# 4x4-keyboard.net
KiCad netlist of a schematic drawn in EAGLE
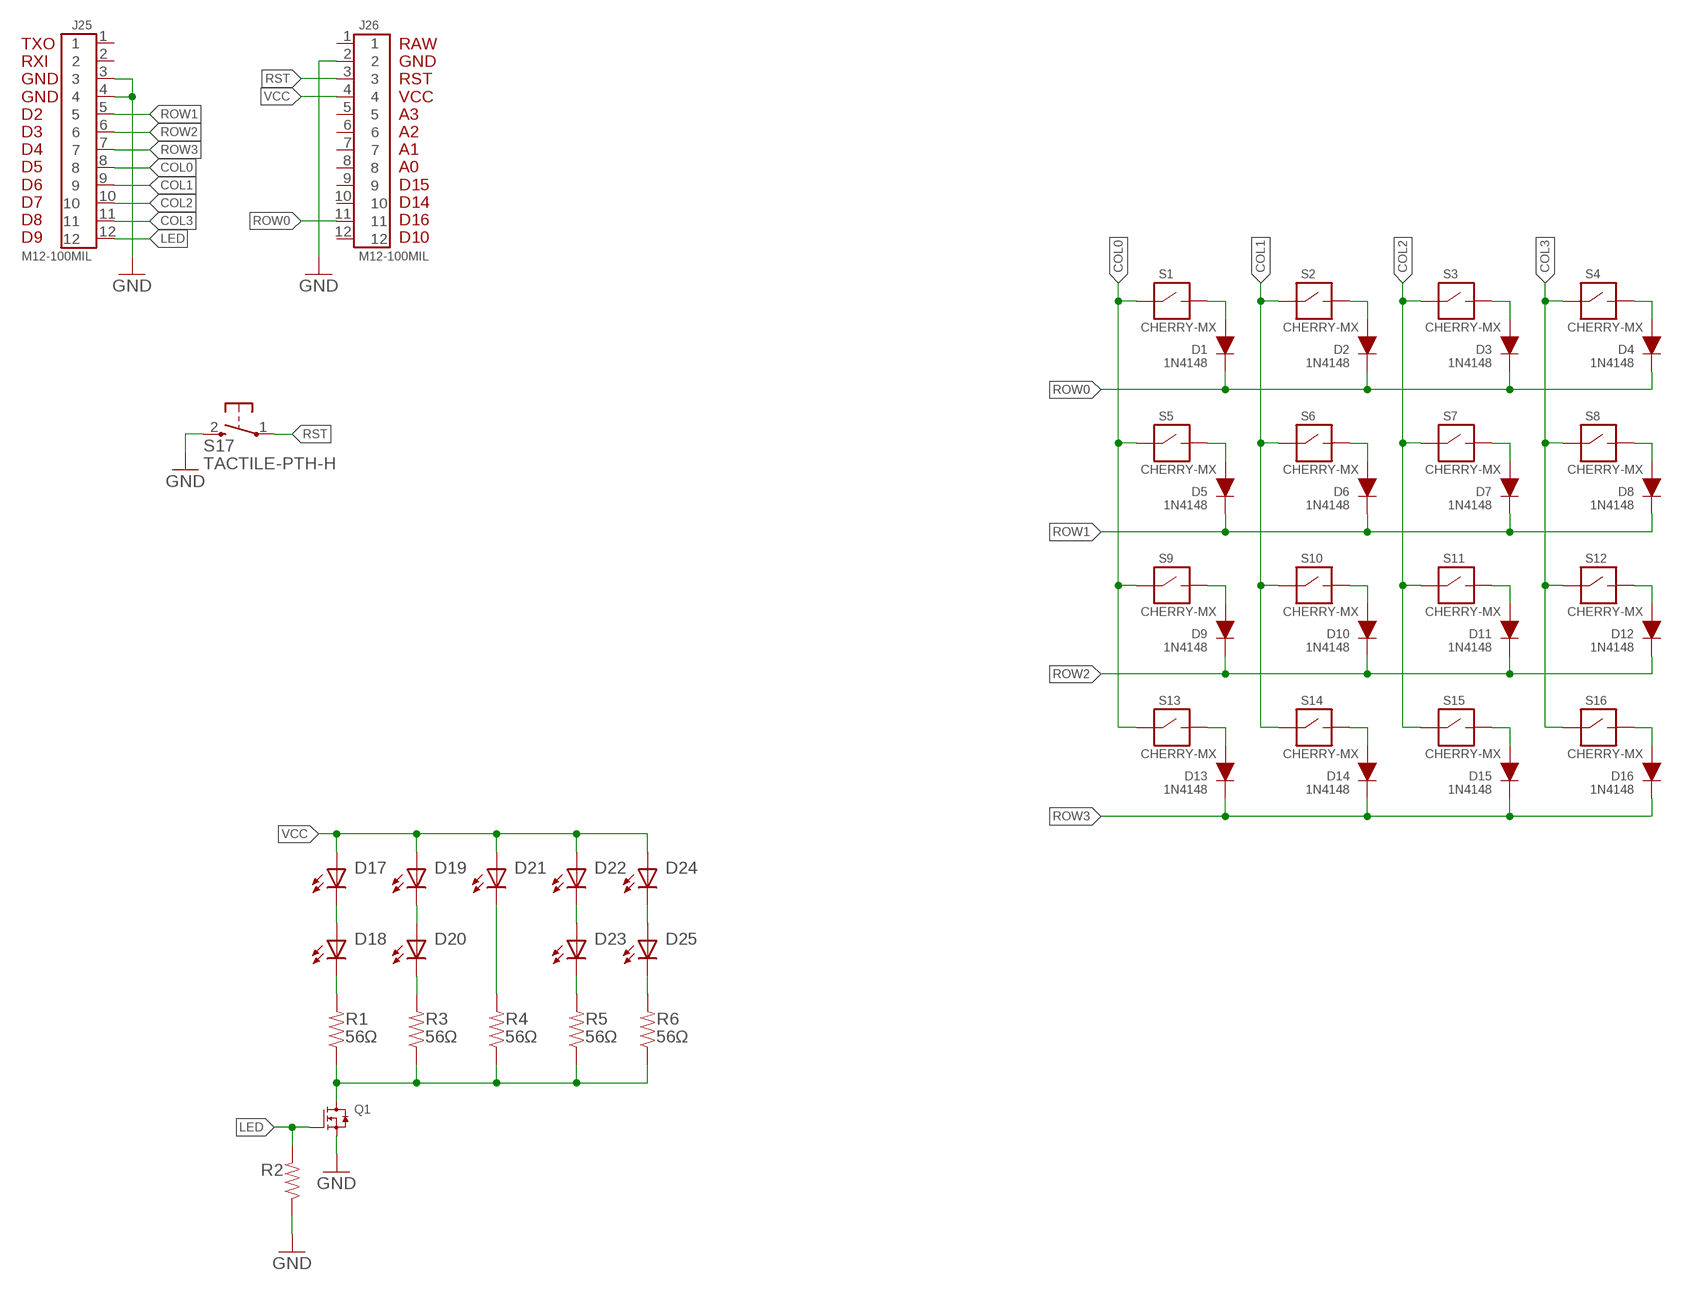
[diagram p0: schematic, sheet 1]

(export (version "E")
  (design (tool "Eeschema 10.0.6"))
  (components
    (comp (ref "D1")
      (value "1N4148")
      (footprint "eagle-import:DIODE-PTH")
      (libsource (lib "eagle-import") (part "DIODE-PTH"))
    )
    (comp (ref "D2")
      (value "1N4148")
      (footprint "eagle-import:DIODE-PTH")
      (libsource (lib "eagle-import") (part "DIODE-PTH"))
    )
    (comp (ref "D3")
      (value "1N4148")
      (footprint "eagle-import:DIODE-PTH")
      (libsource (lib "eagle-import") (part "DIODE-PTH"))
    )
    (comp (ref "D4")
      (value "1N4148")
      (footprint "eagle-import:DIODE-PTH")
      (libsource (lib "eagle-import") (part "DIODE-PTH"))
    )
    (comp (ref "D5")
      (value "1N4148")
      (footprint "eagle-import:DIODE-PTH")
      (libsource (lib "eagle-import") (part "DIODE-PTH"))
    )
    (comp (ref "D6")
      (value "1N4148")
      (footprint "eagle-import:DIODE-PTH")
      (libsource (lib "eagle-import") (part "DIODE-PTH"))
    )
    (comp (ref "D7")
      (value "1N4148")
      (footprint "eagle-import:DIODE-PTH")
      (libsource (lib "eagle-import") (part "DIODE-PTH"))
    )
    (comp (ref "D8")
      (value "1N4148")
      (footprint "eagle-import:DIODE-PTH")
      (libsource (lib "eagle-import") (part "DIODE-PTH"))
    )
    (comp (ref "D9")
      (value "1N4148")
      (footprint "eagle-import:DIODE-PTH")
      (libsource (lib "eagle-import") (part "DIODE-PTH"))
    )
    (comp (ref "D10")
      (value "1N4148")
      (footprint "eagle-import:DIODE-PTH")
      (libsource (lib "eagle-import") (part "DIODE-PTH"))
    )
    (comp (ref "D11")
      (value "1N4148")
      (footprint "eagle-import:DIODE-PTH")
      (libsource (lib "eagle-import") (part "DIODE-PTH"))
    )
    (comp (ref "D12")
      (value "1N4148")
      (footprint "eagle-import:DIODE-PTH")
      (libsource (lib "eagle-import") (part "DIODE-PTH"))
    )
    (comp (ref "D13")
      (value "1N4148")
      (footprint "eagle-import:DIODE-PTH")
      (libsource (lib "eagle-import") (part "DIODE-PTH"))
    )
    (comp (ref "D14")
      (value "1N4148")
      (footprint "eagle-import:DIODE-PTH")
      (libsource (lib "eagle-import") (part "DIODE-PTH"))
    )
    (comp (ref "D15")
      (value "1N4148")
      (footprint "eagle-import:DIODE-PTH")
      (libsource (lib "eagle-import") (part "DIODE-PTH"))
    )
    (comp (ref "D16")
      (value "1N4148")
      (footprint "eagle-import:DIODE-PTH")
      (libsource (lib "eagle-import") (part "DIODE-PTH"))
    )
    (comp (ref "D17")
      (value "LED-3MM")
      (footprint "eagle-import:3MM-LED")
      (libsource (lib "eagle-import") (part "LED-3MM"))
    )
    (comp (ref "D18")
      (value "LED-3MM")
      (footprint "eagle-import:3MM-LED")
      (libsource (lib "eagle-import") (part "LED-3MM"))
    )
    (comp (ref "D19")
      (value "LED-3MM")
      (footprint "eagle-import:3MM-LED")
      (libsource (lib "eagle-import") (part "LED-3MM"))
    )
    (comp (ref "D20")
      (value "LED-3MM")
      (footprint "eagle-import:3MM-LED")
      (libsource (lib "eagle-import") (part "LED-3MM"))
    )
    (comp (ref "D21")
      (value "LED-3MM")
      (footprint "eagle-import:3MM-LED")
      (libsource (lib "eagle-import") (part "LED-3MM"))
    )
    (comp (ref "D22")
      (value "LED-3MM")
      (footprint "eagle-import:3MM-LED")
      (libsource (lib "eagle-import") (part "LED-3MM"))
    )
    (comp (ref "D23")
      (value "LED-3MM")
      (footprint "eagle-import:3MM-LED")
      (libsource (lib "eagle-import") (part "LED-3MM"))
    )
    (comp (ref "D24")
      (value "LED-3MM")
      (footprint "eagle-import:3MM-LED")
      (libsource (lib "eagle-import") (part "LED-3MM"))
    )
    (comp (ref "D25")
      (value "LED-3MM")
      (footprint "eagle-import:3MM-LED")
      (libsource (lib "eagle-import") (part "LED-3MM"))
    )
    (comp (ref "J25")
      (value "M12-100MIL")
      (footprint "eagle-import:M12X1")
      (libsource (lib "eagle-import") (part "M12-100MIL"))
    )
    (comp (ref "J26")
      (value "M12-100MIL")
      (footprint "eagle-import:M12X1")
      (libsource (lib "eagle-import") (part "M12-100MIL"))
    )
    (comp (ref "Q1")
      (value "N-MOSFET-TO-92")
      (footprint "eagle-import:TO-92-3")
      (libsource (lib "eagle-import") (part "N-MOSFET-TO-92"))
    )
    (comp (ref "R1")
      (value "56Ω")
      (footprint "eagle-import:RESISTOR-PTH")
      (libsource (lib "eagle-import") (part "RESISTOR-PTH"))
    )
    (comp (ref "R2")
      (value "RESISTOR-PTH")
      (footprint "eagle-import:RESISTOR-PTH")
      (libsource (lib "eagle-import") (part "RESISTOR-PTH"))
    )
    (comp (ref "R3")
      (value "56Ω")
      (footprint "eagle-import:RESISTOR-PTH")
      (libsource (lib "eagle-import") (part "RESISTOR-PTH"))
    )
    (comp (ref "R4")
      (value "56Ω")
      (footprint "eagle-import:RESISTOR-PTH")
      (libsource (lib "eagle-import") (part "RESISTOR-PTH"))
    )
    (comp (ref "R5")
      (value "56Ω")
      (footprint "eagle-import:RESISTOR-PTH")
      (libsource (lib "eagle-import") (part "RESISTOR-PTH"))
    )
    (comp (ref "R6")
      (value "56Ω")
      (footprint "eagle-import:RESISTOR-PTH")
      (libsource (lib "eagle-import") (part "RESISTOR-PTH"))
    )
    (comp (ref "S1")
      (value "CHERRY-MX")
      (footprint "eagle-import:CHERRY-MX")
      (libsource (lib "eagle-import") (part "CHERRY-MX"))
    )
    (comp (ref "S2")
      (value "CHERRY-MX")
      (footprint "eagle-import:CHERRY-MX")
      (libsource (lib "eagle-import") (part "CHERRY-MX"))
    )
    (comp (ref "S3")
      (value "CHERRY-MX")
      (footprint "eagle-import:CHERRY-MX")
      (libsource (lib "eagle-import") (part "CHERRY-MX"))
    )
    (comp (ref "S4")
      (value "CHERRY-MX")
      (footprint "eagle-import:CHERRY-MX")
      (libsource (lib "eagle-import") (part "CHERRY-MX"))
    )
    (comp (ref "S5")
      (value "CHERRY-MX")
      (footprint "eagle-import:CHERRY-MX")
      (libsource (lib "eagle-import") (part "CHERRY-MX"))
    )
    (comp (ref "S6")
      (value "CHERRY-MX")
      (footprint "eagle-import:CHERRY-MX")
      (libsource (lib "eagle-import") (part "CHERRY-MX"))
    )
    (comp (ref "S7")
      (value "CHERRY-MX")
      (footprint "eagle-import:CHERRY-MX")
      (libsource (lib "eagle-import") (part "CHERRY-MX"))
    )
    (comp (ref "S8")
      (value "CHERRY-MX")
      (footprint "eagle-import:CHERRY-MX")
      (libsource (lib "eagle-import") (part "CHERRY-MX"))
    )
    (comp (ref "S9")
      (value "CHERRY-MX")
      (footprint "eagle-import:CHERRY-MX")
      (libsource (lib "eagle-import") (part "CHERRY-MX"))
    )
    (comp (ref "S10")
      (value "CHERRY-MX")
      (footprint "eagle-import:CHERRY-MX")
      (libsource (lib "eagle-import") (part "CHERRY-MX"))
    )
    (comp (ref "S11")
      (value "CHERRY-MX")
      (footprint "eagle-import:CHERRY-MX")
      (libsource (lib "eagle-import") (part "CHERRY-MX"))
    )
    (comp (ref "S12")
      (value "CHERRY-MX")
      (footprint "eagle-import:CHERRY-MX")
      (libsource (lib "eagle-import") (part "CHERRY-MX"))
    )
    (comp (ref "S13")
      (value "CHERRY-MX")
      (footprint "eagle-import:CHERRY-MX")
      (libsource (lib "eagle-import") (part "CHERRY-MX"))
    )
    (comp (ref "S14")
      (value "CHERRY-MX")
      (footprint "eagle-import:CHERRY-MX")
      (libsource (lib "eagle-import") (part "CHERRY-MX"))
    )
    (comp (ref "S15")
      (value "CHERRY-MX")
      (footprint "eagle-import:CHERRY-MX")
      (libsource (lib "eagle-import") (part "CHERRY-MX"))
    )
    (comp (ref "S16")
      (value "CHERRY-MX")
      (footprint "eagle-import:CHERRY-MX")
      (libsource (lib "eagle-import") (part "CHERRY-MX"))
    )
    (comp (ref "S17")
      (value "TACTILE-PTH-H")
      (footprint "eagle-import:TACTILE-HORIZONTAL")
      (libsource (lib "eagle-import") (part "TACTILE-PTH-H"))
    )
  )
  (nets
    (net (code "1") (name "COL0") (class "Default")
      (node (ref "J25") (pin "8") (pinfunction "8_8") (pintype "bidirectional"))
      (node (ref "S1") (pin "S1") (pinfunction "S1_S1") (pintype "passive"))
      (node (ref "S1") (pin "S4") (pinfunction "S1_S4") (pintype "passive"))
      (node (ref "S13") (pin "S1") (pinfunction "S1_S1") (pintype "passive"))
      (node (ref "S13") (pin "S4") (pinfunction "S1_S4") (pintype "passive"))
      (node (ref "S5") (pin "S1") (pinfunction "S1_S1") (pintype "passive"))
      (node (ref "S5") (pin "S4") (pinfunction "S1_S4") (pintype "passive"))
      (node (ref "S9") (pin "S1") (pinfunction "S1_S1") (pintype "passive"))
      (node (ref "S9") (pin "S4") (pinfunction "S1_S4") (pintype "passive"))
    )
    (net (code "2") (name "COL1") (class "Default")
      (node (ref "J25") (pin "9") (pinfunction "9_9") (pintype "bidirectional"))
      (node (ref "S10") (pin "S1") (pinfunction "S1_S1") (pintype "passive"))
      (node (ref "S10") (pin "S4") (pinfunction "S1_S4") (pintype "passive"))
      (node (ref "S14") (pin "S1") (pinfunction "S1_S1") (pintype "passive"))
      (node (ref "S14") (pin "S4") (pinfunction "S1_S4") (pintype "passive"))
      (node (ref "S2") (pin "S1") (pinfunction "S1_S1") (pintype "passive"))
      (node (ref "S2") (pin "S4") (pinfunction "S1_S4") (pintype "passive"))
      (node (ref "S6") (pin "S1") (pinfunction "S1_S1") (pintype "passive"))
      (node (ref "S6") (pin "S4") (pinfunction "S1_S4") (pintype "passive"))
    )
    (net (code "3") (name "COL2") (class "Default")
      (node (ref "J25") (pin "10") (pinfunction "10_10") (pintype "bidirectional"))
      (node (ref "S11") (pin "S1") (pinfunction "S1_S1") (pintype "passive"))
      (node (ref "S11") (pin "S4") (pinfunction "S1_S4") (pintype "passive"))
      (node (ref "S15") (pin "S1") (pinfunction "S1_S1") (pintype "passive"))
      (node (ref "S15") (pin "S4") (pinfunction "S1_S4") (pintype "passive"))
      (node (ref "S3") (pin "S1") (pinfunction "S1_S1") (pintype "passive"))
      (node (ref "S3") (pin "S4") (pinfunction "S1_S4") (pintype "passive"))
      (node (ref "S7") (pin "S1") (pinfunction "S1_S1") (pintype "passive"))
      (node (ref "S7") (pin "S4") (pinfunction "S1_S4") (pintype "passive"))
    )
    (net (code "4") (name "COL3") (class "Default")
      (node (ref "J25") (pin "11") (pinfunction "11_11") (pintype "bidirectional"))
      (node (ref "S12") (pin "S1") (pinfunction "S1_S1") (pintype "passive"))
      (node (ref "S12") (pin "S4") (pinfunction "S1_S4") (pintype "passive"))
      (node (ref "S16") (pin "S1") (pinfunction "S1_S1") (pintype "passive"))
      (node (ref "S16") (pin "S4") (pinfunction "S1_S4") (pintype "passive"))
      (node (ref "S4") (pin "S1") (pinfunction "S1_S1") (pintype "passive"))
      (node (ref "S4") (pin "S4") (pinfunction "S1_S4") (pintype "passive"))
      (node (ref "S8") (pin "S1") (pinfunction "S1_S1") (pintype "passive"))
      (node (ref "S8") (pin "S4") (pinfunction "S1_S4") (pintype "passive"))
    )
    (net (code "5") (name "GND") (class "Default")
      (node (ref "J25") (pin "3") (pinfunction "3_3") (pintype "bidirectional"))
      (node (ref "J25") (pin "4") (pinfunction "4_4") (pintype "bidirectional"))
      (node (ref "J26") (pin "2") (pinfunction "2_2") (pintype "bidirectional"))
      (node (ref "Q1") (pin "1") (pinfunction "SOURCE_1") (pintype "bidirectional"))
      (node (ref "R2") (pin "P$1") (pinfunction "1_P$1") (pintype "passive"))
      (node (ref "S17") (pin "2") (pinfunction "3_2") (pintype "passive"))
    )
    (net (code "6") (name "LED") (class "Default")
      (node (ref "J25") (pin "12") (pinfunction "12_12") (pintype "bidirectional"))
      (node (ref "Q1") (pin "2") (pinfunction "GATE_2") (pintype "bidirectional"))
      (node (ref "R2") (pin "P$2") (pinfunction "2_P$2") (pintype "passive"))
    )
    (net (code "7") (name "Net-(D1-PadA)") (class "Default")
      (node (ref "D1") (pin "A") (pinfunction "A_A") (pintype "bidirectional"))
      (node (ref "S1") (pin "S2") (pinfunction "S2_S2") (pintype "passive"))
      (node (ref "S1") (pin "S3") (pinfunction "S2_S3") (pintype "passive"))
    )
    (net (code "8") (name "Net-(D2-PadA)") (class "Default")
      (node (ref "D2") (pin "A") (pinfunction "A_A") (pintype "bidirectional"))
      (node (ref "S2") (pin "S2") (pinfunction "S2_S2") (pintype "passive"))
      (node (ref "S2") (pin "S3") (pinfunction "S2_S3") (pintype "passive"))
    )
    (net (code "9") (name "Net-(D3-PadA)") (class "Default")
      (node (ref "D3") (pin "A") (pinfunction "A_A") (pintype "bidirectional"))
      (node (ref "S3") (pin "S2") (pinfunction "S2_S2") (pintype "passive"))
      (node (ref "S3") (pin "S3") (pinfunction "S2_S3") (pintype "passive"))
    )
    (net (code "10") (name "Net-(D4-PadA)") (class "Default")
      (node (ref "D4") (pin "A") (pinfunction "A_A") (pintype "bidirectional"))
      (node (ref "S4") (pin "S2") (pinfunction "S2_S2") (pintype "passive"))
      (node (ref "S4") (pin "S3") (pinfunction "S2_S3") (pintype "passive"))
    )
    (net (code "11") (name "Net-(D5-PadA)") (class "Default")
      (node (ref "D5") (pin "A") (pinfunction "A_A") (pintype "bidirectional"))
      (node (ref "S5") (pin "S2") (pinfunction "S2_S2") (pintype "passive"))
      (node (ref "S5") (pin "S3") (pinfunction "S2_S3") (pintype "passive"))
    )
    (net (code "12") (name "Net-(D6-PadA)") (class "Default")
      (node (ref "D6") (pin "A") (pinfunction "A_A") (pintype "bidirectional"))
      (node (ref "S6") (pin "S2") (pinfunction "S2_S2") (pintype "passive"))
      (node (ref "S6") (pin "S3") (pinfunction "S2_S3") (pintype "passive"))
    )
    (net (code "13") (name "Net-(D7-PadA)") (class "Default")
      (node (ref "D7") (pin "A") (pinfunction "A_A") (pintype "bidirectional"))
      (node (ref "S7") (pin "S2") (pinfunction "S2_S2") (pintype "passive"))
      (node (ref "S7") (pin "S3") (pinfunction "S2_S3") (pintype "passive"))
    )
    (net (code "14") (name "Net-(D8-PadA)") (class "Default")
      (node (ref "D8") (pin "A") (pinfunction "A_A") (pintype "bidirectional"))
      (node (ref "S8") (pin "S2") (pinfunction "S2_S2") (pintype "passive"))
      (node (ref "S8") (pin "S3") (pinfunction "S2_S3") (pintype "passive"))
    )
    (net (code "15") (name "Net-(D9-PadA)") (class "Default")
      (node (ref "D9") (pin "A") (pinfunction "A_A") (pintype "bidirectional"))
      (node (ref "S9") (pin "S2") (pinfunction "S2_S2") (pintype "passive"))
      (node (ref "S9") (pin "S3") (pinfunction "S2_S3") (pintype "passive"))
    )
    (net (code "16") (name "Net-(D10-PadA)") (class "Default")
      (node (ref "D10") (pin "A") (pinfunction "A_A") (pintype "bidirectional"))
      (node (ref "S10") (pin "S2") (pinfunction "S2_S2") (pintype "passive"))
      (node (ref "S10") (pin "S3") (pinfunction "S2_S3") (pintype "passive"))
    )
    (net (code "17") (name "Net-(D11-PadA)") (class "Default")
      (node (ref "D11") (pin "A") (pinfunction "A_A") (pintype "bidirectional"))
      (node (ref "S11") (pin "S2") (pinfunction "S2_S2") (pintype "passive"))
      (node (ref "S11") (pin "S3") (pinfunction "S2_S3") (pintype "passive"))
    )
    (net (code "18") (name "Net-(D12-PadA)") (class "Default")
      (node (ref "D12") (pin "A") (pinfunction "A_A") (pintype "bidirectional"))
      (node (ref "S12") (pin "S2") (pinfunction "S2_S2") (pintype "passive"))
      (node (ref "S12") (pin "S3") (pinfunction "S2_S3") (pintype "passive"))
    )
    (net (code "19") (name "Net-(D13-PadA)") (class "Default")
      (node (ref "D13") (pin "A") (pinfunction "A_A") (pintype "bidirectional"))
      (node (ref "S13") (pin "S2") (pinfunction "S2_S2") (pintype "passive"))
      (node (ref "S13") (pin "S3") (pinfunction "S2_S3") (pintype "passive"))
    )
    (net (code "20") (name "Net-(D14-PadA)") (class "Default")
      (node (ref "D14") (pin "A") (pinfunction "A_A") (pintype "bidirectional"))
      (node (ref "S14") (pin "S2") (pinfunction "S2_S2") (pintype "passive"))
      (node (ref "S14") (pin "S3") (pinfunction "S2_S3") (pintype "passive"))
    )
    (net (code "21") (name "Net-(D15-PadA)") (class "Default")
      (node (ref "D15") (pin "A") (pinfunction "A_A") (pintype "bidirectional"))
      (node (ref "S15") (pin "S2") (pinfunction "S2_S2") (pintype "passive"))
      (node (ref "S15") (pin "S3") (pinfunction "S2_S3") (pintype "passive"))
    )
    (net (code "22") (name "Net-(D16-PadA)") (class "Default")
      (node (ref "D16") (pin "A") (pinfunction "A_A") (pintype "bidirectional"))
      (node (ref "S16") (pin "S2") (pinfunction "S2_S2") (pintype "passive"))
      (node (ref "S16") (pin "S3") (pinfunction "S2_S3") (pintype "passive"))
    )
    (net (code "23") (name "Net-(D17-PadC)") (class "Default")
      (node (ref "D17") (pin "C") (pinfunction "C_C") (pintype "passive"))
      (node (ref "D18") (pin "A") (pinfunction "A_A") (pintype "passive"))
    )
    (net (code "24") (name "Net-(D19-PadC)") (class "Default")
      (node (ref "D19") (pin "C") (pinfunction "C_C") (pintype "passive"))
      (node (ref "D20") (pin "A") (pinfunction "A_A") (pintype "passive"))
    )
    (net (code "25") (name "Net-(D22-PadC)") (class "Default")
      (node (ref "D22") (pin "C") (pinfunction "C_C") (pintype "passive"))
      (node (ref "D23") (pin "A") (pinfunction "A_A") (pintype "passive"))
    )
    (net (code "26") (name "Net-(D24-PadC)") (class "Default")
      (node (ref "D24") (pin "C") (pinfunction "C_C") (pintype "passive"))
      (node (ref "D25") (pin "A") (pinfunction "A_A") (pintype "passive"))
    )
    (net (code "27") (name "Net-(Q1-DRAIN)") (class "Default")
      (node (ref "Q1") (pin "3") (pinfunction "DRAIN_3") (pintype "bidirectional"))
      (node (ref "R1") (pin "P$1") (pinfunction "1_P$1") (pintype "passive"))
      (node (ref "R3") (pin "P$1") (pinfunction "1_P$1") (pintype "passive"))
      (node (ref "R4") (pin "P$1") (pinfunction "1_P$1") (pintype "passive"))
      (node (ref "R5") (pin "P$1") (pinfunction "1_P$1") (pintype "passive"))
      (node (ref "R6") (pin "P$1") (pinfunction "1_P$1") (pintype "passive"))
    )
    (net (code "28") (name "Net-(R1-2)") (class "Default")
      (node (ref "D18") (pin "C") (pinfunction "C_C") (pintype "passive"))
      (node (ref "R1") (pin "P$2") (pinfunction "2_P$2") (pintype "passive"))
    )
    (net (code "29") (name "Net-(R3-2)") (class "Default")
      (node (ref "D20") (pin "C") (pinfunction "C_C") (pintype "passive"))
      (node (ref "R3") (pin "P$2") (pinfunction "2_P$2") (pintype "passive"))
    )
    (net (code "30") (name "Net-(R4-2)") (class "Default")
      (node (ref "D21") (pin "C") (pinfunction "C_C") (pintype "passive"))
      (node (ref "R4") (pin "P$2") (pinfunction "2_P$2") (pintype "passive"))
    )
    (net (code "31") (name "Net-(R5-2)") (class "Default")
      (node (ref "D23") (pin "C") (pinfunction "C_C") (pintype "passive"))
      (node (ref "R5") (pin "P$2") (pinfunction "2_P$2") (pintype "passive"))
    )
    (net (code "32") (name "Net-(R6-2)") (class "Default")
      (node (ref "D25") (pin "C") (pinfunction "C_C") (pintype "passive"))
      (node (ref "R6") (pin "P$2") (pinfunction "2_P$2") (pintype "passive"))
    )
    (net (code "33") (name "ROW0") (class "Default")
      (node (ref "D1") (pin "C") (pinfunction "C_C") (pintype "bidirectional"))
      (node (ref "D2") (pin "C") (pinfunction "C_C") (pintype "bidirectional"))
      (node (ref "D3") (pin "C") (pinfunction "C_C") (pintype "bidirectional"))
      (node (ref "D4") (pin "C") (pinfunction "C_C") (pintype "bidirectional"))
      (node (ref "J26") (pin "11") (pinfunction "11_11") (pintype "bidirectional"))
    )
    (net (code "34") (name "ROW1") (class "Default")
      (node (ref "D5") (pin "C") (pinfunction "C_C") (pintype "bidirectional"))
      (node (ref "D6") (pin "C") (pinfunction "C_C") (pintype "bidirectional"))
      (node (ref "D7") (pin "C") (pinfunction "C_C") (pintype "bidirectional"))
      (node (ref "D8") (pin "C") (pinfunction "C_C") (pintype "bidirectional"))
      (node (ref "J25") (pin "5") (pinfunction "5_5") (pintype "bidirectional"))
    )
    (net (code "35") (name "ROW2") (class "Default")
      (node (ref "D10") (pin "C") (pinfunction "C_C") (pintype "bidirectional"))
      (node (ref "D11") (pin "C") (pinfunction "C_C") (pintype "bidirectional"))
      (node (ref "D12") (pin "C") (pinfunction "C_C") (pintype "bidirectional"))
      (node (ref "D9") (pin "C") (pinfunction "C_C") (pintype "bidirectional"))
      (node (ref "J25") (pin "6") (pinfunction "6_6") (pintype "bidirectional"))
    )
    (net (code "36") (name "ROW3") (class "Default")
      (node (ref "D13") (pin "C") (pinfunction "C_C") (pintype "bidirectional"))
      (node (ref "D14") (pin "C") (pinfunction "C_C") (pintype "bidirectional"))
      (node (ref "D15") (pin "C") (pinfunction "C_C") (pintype "bidirectional"))
      (node (ref "D16") (pin "C") (pinfunction "C_C") (pintype "bidirectional"))
      (node (ref "J25") (pin "7") (pinfunction "7_7") (pintype "bidirectional"))
    )
    (net (code "37") (name "RST") (class "Default")
      (node (ref "J26") (pin "3") (pinfunction "3_3") (pintype "bidirectional"))
      (node (ref "S17") (pin "1") (pinfunction "1_1") (pintype "passive"))
    )
    (net (code "38") (name "VCC") (class "Default")
      (node (ref "D17") (pin "A") (pinfunction "A_A") (pintype "passive"))
      (node (ref "D19") (pin "A") (pinfunction "A_A") (pintype "passive"))
      (node (ref "D21") (pin "A") (pinfunction "A_A") (pintype "passive"))
      (node (ref "D22") (pin "A") (pinfunction "A_A") (pintype "passive"))
      (node (ref "D24") (pin "A") (pinfunction "A_A") (pintype "passive"))
      (node (ref "J26") (pin "4") (pinfunction "4_4") (pintype "bidirectional"))
    )
    (net (code "39") (name "unconnected-(J25-Pad1)") (class "Default")
      (node (ref "J25") (pin "1") (pinfunction "1_1") (pintype "bidirectional"))
    )
    (net (code "40") (name "unconnected-(J25-Pad2)") (class "Default")
      (node (ref "J25") (pin "2") (pinfunction "2_2") (pintype "bidirectional"))
    )
    (net (code "41") (name "unconnected-(J26-Pad1)") (class "Default")
      (node (ref "J26") (pin "1") (pinfunction "1_1") (pintype "bidirectional"))
    )
    (net (code "42") (name "unconnected-(J26-Pad5)") (class "Default")
      (node (ref "J26") (pin "5") (pinfunction "5_5") (pintype "bidirectional"))
    )
    (net (code "43") (name "unconnected-(J26-Pad6)") (class "Default")
      (node (ref "J26") (pin "6") (pinfunction "6_6") (pintype "bidirectional"))
    )
    (net (code "44") (name "unconnected-(J26-Pad7)") (class "Default")
      (node (ref "J26") (pin "7") (pinfunction "7_7") (pintype "bidirectional"))
    )
    (net (code "45") (name "unconnected-(J26-Pad8)") (class "Default")
      (node (ref "J26") (pin "8") (pinfunction "8_8") (pintype "bidirectional"))
    )
    (net (code "46") (name "unconnected-(J26-Pad9)") (class "Default")
      (node (ref "J26") (pin "9") (pinfunction "9_9") (pintype "bidirectional"))
    )
    (net (code "47") (name "unconnected-(J26-Pad10)") (class "Default")
      (node (ref "J26") (pin "10") (pinfunction "10_10") (pintype "bidirectional"))
    )
    (net (code "48") (name "unconnected-(J26-Pad12)") (class "Default")
      (node (ref "J26") (pin "12") (pinfunction "12_12") (pintype "bidirectional"))
    )
  )
)
